# TMC2208.net
KiCad netlist of a schematic drawn in Altium Designer
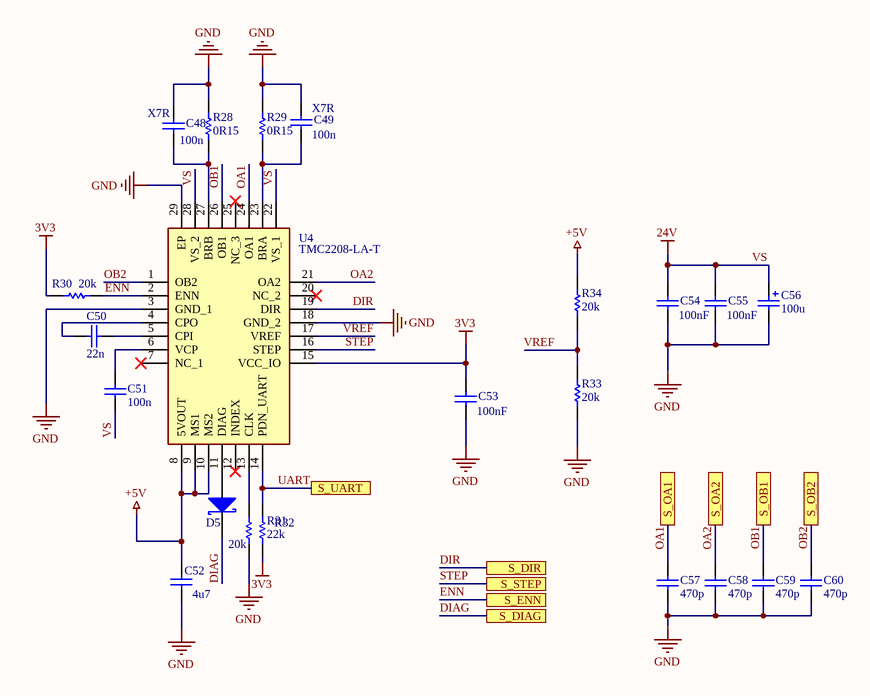
[diagram p0: TMC2208.SchDoc]

(export (version "E")
  (design (tool "Eeschema 10.0.6"))
  (components
    (comp (ref "C48")
      (value "X7R")
      (footprint "RAD-0.3")
      (description "Capacitor")
      (fields (field (name "ALTIUM_VALUE") "100n") (field (name "PUBLISHER") "Altium Limited"))
      (libsource (lib "Miscellaneous Devices") (part "Cap"))
    )
    (comp (ref "C49")
      (value "X7R")
      (footprint "RAD-0.3")
      (description "Capacitor")
      (fields (field (name "ALTIUM_VALUE") "100n") (field (name "PUBLISHER") "Altium Limited"))
      (libsource (lib "Miscellaneous Devices") (part "Cap"))
    )
    (comp (ref "C50")
      (value "22n")
      (footprint "RAD-0.3")
      (description "Capacitor")
      (fields (field (name "Comment") "X5R") (field (name "PUBLISHER") "Altium Limited"))
      (libsource (lib "Miscellaneous Devices") (part "Cap"))
    )
    (comp (ref "C51")
      (value "100n")
      (footprint "RAD-0.3")
      (description "Capacitor")
      (fields (field (name "Comment") "X5R") (field (name "PUBLISHER") "Altium Limited"))
      (libsource (lib "Miscellaneous Devices") (part "Cap"))
    )
    (comp (ref "C52")
      (value "4u7")
      (footprint "RAD-0.3")
      (description "Capacitor")
      (fields (field (name "Comment") "X5R") (field (name "PUBLISHER") "Altium Limited"))
      (libsource (lib "Miscellaneous Devices") (part "Cap"))
    )
    (comp (ref "C53")
      (value "100nF")
      (footprint "RAD-0.3")
      (description "Capacitor")
      (fields (field (name "Comment") "X5R") (field (name "PUBLISHER") "Altium Limited"))
      (libsource (lib "Miscellaneous Devices") (part "Cap"))
    )
    (comp (ref "C54")
      (value "100nF")
      (footprint "RAD-0.3")
      (description "Capacitor")
      (fields (field (name "Comment") "X5R") (field (name "PUBLISHER") "Altium Limited"))
      (libsource (lib "Miscellaneous Devices") (part "Cap"))
    )
    (comp (ref "C55")
      (value "100nF")
      (footprint "RAD-0.3")
      (description "Capacitor")
      (fields (field (name "Comment") "X5R") (field (name "PUBLISHER") "Altium Limited"))
      (libsource (lib "Miscellaneous Devices") (part "Cap"))
    )
    (comp (ref "C56")
      (value "100u")
      (footprint "TAN-B")
      (description "Polarized Capacitor (Radial)")
      (fields (field (name "PUBLISHER") "Altium Limited"))
      (libsource (lib "MB1137") (part "Cap Pol1"))
    )
    (comp (ref "C57")
      (value "470p")
      (footprint "RAD-0.3")
      (description "Capacitor")
      (fields (field (name "Comment") "X5R") (field (name "PUBLISHER") "Altium Limited"))
      (libsource (lib "Miscellaneous Devices") (part "Cap"))
    )
    (comp (ref "C58")
      (value "470p")
      (footprint "RAD-0.3")
      (description "Capacitor")
      (fields (field (name "Comment") "X5R") (field (name "PUBLISHER") "Altium Limited"))
      (libsource (lib "Miscellaneous Devices") (part "Cap"))
    )
    (comp (ref "C59")
      (value "470p")
      (footprint "RAD-0.3")
      (description "Capacitor")
      (fields (field (name "Comment") "X5R") (field (name "PUBLISHER") "Altium Limited"))
      (libsource (lib "Miscellaneous Devices") (part "Cap"))
    )
    (comp (ref "C60")
      (value "470p")
      (footprint "RAD-0.3")
      (description "Capacitor")
      (fields (field (name "Comment") "X5R") (field (name "PUBLISHER") "Altium Limited"))
      (libsource (lib "Miscellaneous Devices") (part "Cap"))
    )
    (comp (ref "D5")
      (value "Diode BAT17")
      (footprint "SOT-23_N")
      (description "Silicon RF Schottky Diode for Mixer Applications in the VHF/UHF Range")
      (fields (field (name "PUBLISHER") "Altium Limited"))
      (libsource (lib "Miscellaneous Devices") (part "Diode BAT17"))
    )
    (comp (ref "R28")
      (value "0R15")
      (footprint "AXIAL-0.3")
      (description "Resistor")
      (fields (field (name "Comment") "Res1") (field (name "PUBLISHER") "Altium Limited"))
      (libsource (lib "Miscellaneous Devices") (part "Res1"))
    )
    (comp (ref "R29")
      (value "0R15")
      (footprint "AXIAL-0.3")
      (description "Resistor")
      (fields (field (name "Comment") "Res1") (field (name "PUBLISHER") "Altium Limited"))
      (libsource (lib "Miscellaneous Devices") (part "Res1"))
    )
    (comp (ref "R30")
      (value "20k")
      (footprint "AXIAL-0.3")
      (description "Resistor")
      (fields (field (name "Comment") "Res1") (field (name "PUBLISHER") "Altium Limited"))
      (libsource (lib "Miscellaneous Devices") (part "Res1"))
    )
    (comp (ref "R31")
      (value "22k")
      (footprint "AXIAL-0.3")
      (description "Resistor")
      (fields (field (name "Comment") "Res1") (field (name "PUBLISHER") "Altium Limited"))
      (libsource (lib "Miscellaneous Devices") (part "Res1"))
    )
    (comp (ref "R32")
      (value "20k")
      (footprint "AXIAL-0.3")
      (description "Resistor")
      (fields (field (name "Comment") "Res1") (field (name "PUBLISHER") "Altium Limited"))
      (libsource (lib "Miscellaneous Devices") (part "Res1"))
    )
    (comp (ref "R33")
      (value "20k")
      (footprint "AXIAL-0.3")
      (description "Resistor")
      (fields (field (name "Comment") "Res1") (field (name "PUBLISHER") "Altium Limited"))
      (libsource (lib "Miscellaneous Devices") (part "Res1"))
    )
    (comp (ref "R34")
      (value "20k")
      (footprint "AXIAL-0.3")
      (description "Resistor")
      (fields (field (name "Comment") "Res1") (field (name "PUBLISHER") "Altium Limited"))
      (libsource (lib "Miscellaneous Devices") (part "Res1"))
    )
    (comp (ref "U4")
      (value "TMC2208-LA-T")
      (footprint "SamacSys:QFN50P500X500X90-29N-D")
      (description "Integrated Circuit")
      (fields (field (name "MOUSER PART NUMBER") "700-TMC2208-LA-T"))
      (libsource (lib "*") (part "TMC2208-LA-T"))
    )
  )
  (nets
    (net (code "1") (name "+5V") (class "Default")
      (node (ref "C52") (pin "1") (pinfunction "1_1") (pintype "passive"))
      (node (ref "R34") (pin "2") (pinfunction "2_2") (pintype "passive"))
      (node (ref "U4") (pin "10") (pinfunction "MS2_10") (pintype "passive"))
      (node (ref "U4") (pin "8") (pinfunction "5VOUT_8") (pintype "passive"))
      (node (ref "U4") (pin "9") (pinfunction "MS1_9") (pintype "passive"))
    )
    (net (code "2") (name "/DIAG") (class "Default")
      (node (ref "D5") (pin "3") (pinfunction "K_3") (pintype "passive"))
    )
    (net (code "3") (name "/DIR") (class "Default")
      (node (ref "U4") (pin "19") (pinfunction "DIR_19") (pintype "passive"))
    )
    (net (code "4") (name "/ENN") (class "Default")
      (node (ref "R30") (pin "2") (pinfunction "2_2") (pintype "passive"))
      (node (ref "U4") (pin "2") (pinfunction "ENN_2") (pintype "passive"))
    )
    (net (code "5") (name "/OA1") (class "Default")
      (node (ref "C57") (pin "2") (pinfunction "2_2") (pintype "passive"))
      (node (ref "U4") (pin "24") (pinfunction "OA1_24") (pintype "passive"))
    )
    (net (code "6") (name "/OA2") (class "Default")
      (node (ref "C58") (pin "2") (pinfunction "2_2") (pintype "passive"))
      (node (ref "U4") (pin "21") (pinfunction "OA2_21") (pintype "passive"))
    )
    (net (code "7") (name "/OB1") (class "Default")
      (node (ref "C59") (pin "2") (pinfunction "2_2") (pintype "passive"))
      (node (ref "U4") (pin "26") (pinfunction "OB1_26") (pintype "passive"))
    )
    (net (code "8") (name "/OB2") (class "Default")
      (node (ref "C60") (pin "2") (pinfunction "2_2") (pintype "passive"))
      (node (ref "U4") (pin "1") (pinfunction "OB2_1") (pintype "passive"))
    )
    (net (code "9") (name "/STEP") (class "Default")
      (node (ref "U4") (pin "16") (pinfunction "STEP_16") (pintype "passive"))
    )
    (net (code "10") (name "/UART") (class "Default")
      (node (ref "R31") (pin "2") (pinfunction "2_2") (pintype "passive"))
      (node (ref "U4") (pin "14") (pinfunction "PDN_UART_14") (pintype "passive"))
    )
    (net (code "11") (name "/VREF") (class "Default")
      (node (ref "R33") (pin "2") (pinfunction "2_2") (pintype "passive"))
      (node (ref "R34") (pin "1") (pinfunction "1_1") (pintype "passive"))
      (node (ref "U4") (pin "17") (pinfunction "VREF_17") (pintype "passive"))
    )
    (net (code "12") (name "3V3") (class "Default")
      (node (ref "C53") (pin "1") (pinfunction "1_1") (pintype "passive"))
      (node (ref "R30") (pin "1") (pinfunction "1_1") (pintype "passive"))
      (node (ref "R31") (pin "1") (pinfunction "1_1") (pintype "passive"))
      (node (ref "U4") (pin "15") (pinfunction "VCC_IO_15") (pintype "passive"))
    )
    (net (code "13") (name "24V") (class "Default")
      (node (ref "C51") (pin "1") (pinfunction "1_1") (pintype "passive"))
      (node (ref "C54") (pin "1") (pinfunction "1_1") (pintype "passive"))
      (node (ref "C55") (pin "1") (pinfunction "1_1") (pintype "passive"))
      (node (ref "C56") (pin "1") (pinfunction "1_1") (pintype "passive"))
      (node (ref "U4") (pin "22") (pinfunction "VS_1_22") (pintype "passive"))
      (node (ref "U4") (pin "28") (pinfunction "VS_2_28") (pintype "passive"))
    )
    (net (code "14") (name "GND") (class "Default")
      (node (ref "C48") (pin "2") (pinfunction "2_2") (pintype "passive"))
      (node (ref "C49") (pin "1") (pinfunction "1_1") (pintype "passive"))
      (node (ref "C52") (pin "2") (pinfunction "2_2") (pintype "passive"))
      (node (ref "C53") (pin "2") (pinfunction "2_2") (pintype "passive"))
      (node (ref "C54") (pin "2") (pinfunction "2_2") (pintype "passive"))
      (node (ref "C55") (pin "2") (pinfunction "2_2") (pintype "passive"))
      (node (ref "C56") (pin "2") (pinfunction "2_2") (pintype "passive"))
      (node (ref "C57") (pin "1") (pinfunction "1_1") (pintype "passive"))
      (node (ref "C58") (pin "1") (pinfunction "1_1") (pintype "passive"))
      (node (ref "C59") (pin "1") (pinfunction "1_1") (pintype "passive"))
      (node (ref "C60") (pin "1") (pinfunction "1_1") (pintype "passive"))
      (node (ref "R28") (pin "2") (pinfunction "2_2") (pintype "passive"))
      (node (ref "R29") (pin "2") (pinfunction "2_2") (pintype "passive"))
      (node (ref "R32") (pin "1") (pinfunction "1_1") (pintype "passive"))
      (node (ref "R33") (pin "1") (pinfunction "1_1") (pintype "passive"))
      (node (ref "U4") (pin "18") (pinfunction "GND_2_18") (pintype "passive"))
      (node (ref "U4") (pin "29") (pinfunction "EP_29") (pintype "passive"))
      (node (ref "U4") (pin "3") (pinfunction "GND_1_3") (pintype "passive"))
    )
    (net (code "15") (name "Net-(D5-A)") (class "Default")
      (node (ref "D5") (pin "1") (pinfunction "A_1") (pintype "passive"))
      (node (ref "U4") (pin "11") (pinfunction "DIAG_11") (pintype "passive"))
    )
    (net (code "16") (name "Net-(U4-BRA)") (class "Default")
      (node (ref "C49") (pin "2") (pinfunction "2_2") (pintype "passive"))
      (node (ref "R29") (pin "1") (pinfunction "1_1") (pintype "passive"))
      (node (ref "U4") (pin "23") (pinfunction "BRA_23") (pintype "passive"))
    )
    (net (code "17") (name "Net-(U4-BRB)") (class "Default")
      (node (ref "C48") (pin "1") (pinfunction "1_1") (pintype "passive"))
      (node (ref "R28") (pin "1") (pinfunction "1_1") (pintype "passive"))
      (node (ref "U4") (pin "27") (pinfunction "BRB_27") (pintype "passive"))
    )
    (net (code "18") (name "Net-(U4-CLK)") (class "Default")
      (node (ref "R32") (pin "2") (pinfunction "2_2") (pintype "passive"))
      (node (ref "U4") (pin "13") (pinfunction "CLK_13") (pintype "passive"))
    )
    (net (code "19") (name "Net-(U4-CPI)") (class "Default")
      (node (ref "C50") (pin "2") (pinfunction "2_2") (pintype "passive"))
      (node (ref "U4") (pin "5") (pinfunction "CPI_5") (pintype "passive"))
    )
    (net (code "20") (name "Net-(U4-CPO)") (class "Default")
      (node (ref "C50") (pin "1") (pinfunction "1_1") (pintype "passive"))
      (node (ref "U4") (pin "4") (pinfunction "CPO_4") (pintype "passive"))
    )
    (net (code "21") (name "Net-(U4-VCP)") (class "Default")
      (node (ref "C51") (pin "2") (pinfunction "2_2") (pintype "passive"))
      (node (ref "U4") (pin "6") (pinfunction "VCP_6") (pintype "passive"))
    )
    (net (code "22") (name "unconnected-(U4-INDEX-Pad12)") (class "Default")
      (node (ref "U4") (pin "12") (pinfunction "INDEX_12") (pintype "passive+no_connect"))
    )
    (net (code "23") (name "unconnected-(U4-NC_1-Pad7)") (class "Default")
      (node (ref "U4") (pin "7") (pinfunction "NC_1_7") (pintype "passive+no_connect"))
    )
    (net (code "24") (name "unconnected-(U4-NC_2-Pad20)") (class "Default")
      (node (ref "U4") (pin "20") (pinfunction "NC_2_20") (pintype "passive+no_connect"))
    )
    (net (code "25") (name "unconnected-(U4-NC_3-Pad25)") (class "Default")
      (node (ref "U4") (pin "25") (pinfunction "NC_3_25") (pintype "passive+no_connect"))
    )
  )
)
